# 467444_130_3_1-A.net
KiCad netlist of a schematic drawn in Altium Designer
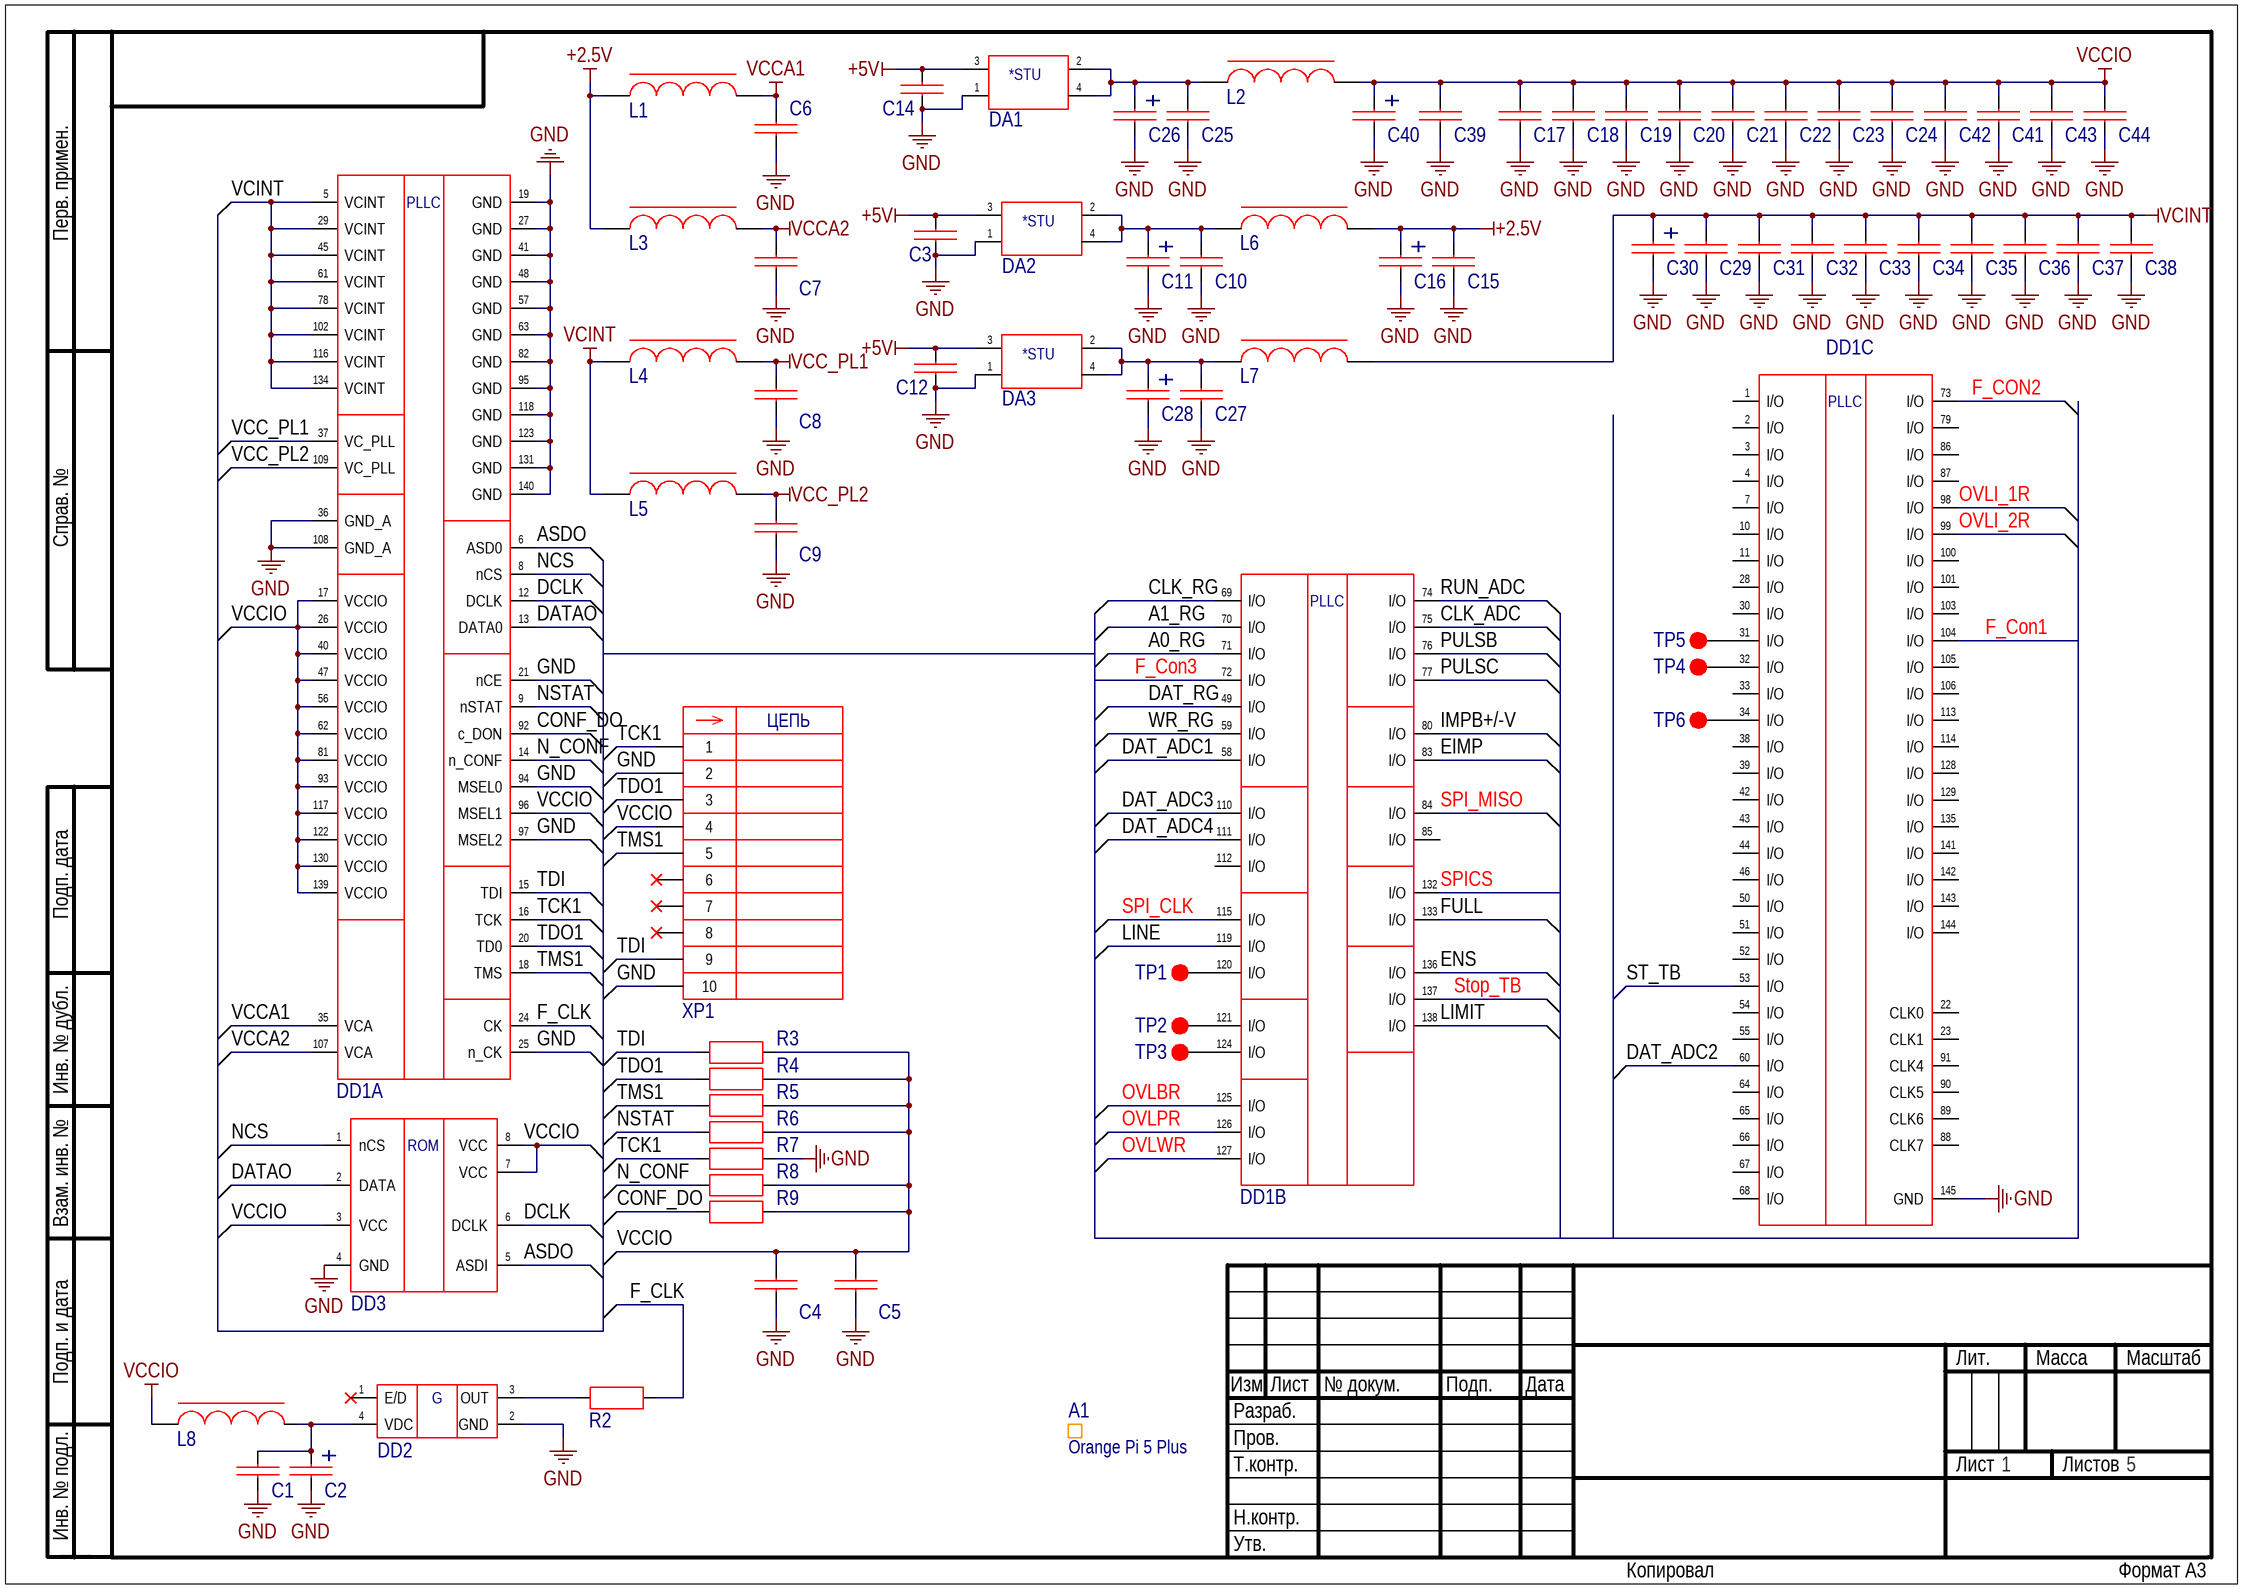
[diagram p0: УШЯИ.467444.130Э3_1-A.SchDoc]

(export (version "E")
  (design (tool "Eeschema 10.0.6"))
  (components
    (comp (ref "A1")
      (value "Orange Pi 5 Plus")
      (footprint "Orange_Pi_5_Plus")
      (description "8GB Rockchip RK3588, HDMI 2.1, Gigabit LAN port, USB2.0/3.0, microSD card slot, USB Type-C")
      (fields (field (name "MANUFACTURER") "Orange Pi"))
      (libsource (lib "lib") (part "0"))
    )
    (comp (ref "C1")
      (value "0,1 µF")
      (footprint "C_0805 [2012 Metric]")
      (description "Неполярный конденсатор")
      (fields (field (name "MANUFACTURER") "Murata") (field (name "VOLTAGE") "50V"))
      (libsource (lib "lib") (part "C_const"))
    )
    (comp (ref "C2")
      (value "4,7 µF")
      (footprint "C+_1210 [3528-21 Metric]")
      (description "Полярный конденсатор")
      (fields (field (name "MANUFACTURER") "KYOCERA AVX") (field (name "VOLTAGE") "20V\r\n10V"))
      (libsource (lib "lib") (part "C_electrolytic"))
    )
    (comp (ref "C3")
      (value "0,1 µF")
      (footprint "C_0805 [2012 Metric]")
      (description "Неполярный конденсатор")
      (fields (field (name "MANUFACTURER") "Murata") (field (name "VOLTAGE") "25V"))
      (libsource (lib "lib") (part "C_const"))
    )
    (comp (ref "C4")
      (value "1 µF")
      (footprint "C_0805 [2012 Metric]")
      (description "Неполярный конденсатор")
      (fields (field (name "MANUFACTURER") "Murata") (field (name "VOLTAGE") "16V"))
      (libsource (lib "lib") (part "C_const"))
    )
    (comp (ref "C5")
      (value "1 µF")
      (footprint "C_0805 [2012 Metric]")
      (description "Неполярный конденсатор")
      (fields (field (name "MANUFACTURER") "Murata") (field (name "VOLTAGE") "16V"))
      (libsource (lib "lib") (part "C_const"))
    )
    (comp (ref "C6")
      (value "0,1 µF")
      (footprint "C_0805 [2012 Metric]")
      (description "Неполярный конденсатор")
      (fields (field (name "MANUFACTURER") "Murata") (field (name "VOLTAGE") "25V"))
      (libsource (lib "lib") (part "C_const"))
    )
    (comp (ref "C7")
      (value "0,1 µF")
      (footprint "C_0805 [2012 Metric]")
      (description "Неполярный конденсатор")
      (fields (field (name "MANUFACTURER") "Murata") (field (name "VOLTAGE") "25V"))
      (libsource (lib "lib") (part "C_const"))
    )
    (comp (ref "C8")
      (value "0,1 µF")
      (footprint "C_0805 [2012 Metric]")
      (description "Неполярный конденсатор")
      (fields (field (name "MANUFACTURER") "Murata") (field (name "VOLTAGE") "25V"))
      (libsource (lib "lib") (part "C_const"))
    )
    (comp (ref "C9")
      (value "0,1 µF")
      (footprint "C_0805 [2012 Metric]")
      (description "Неполярный конденсатор")
      (fields (field (name "MANUFACTURER") "Murata") (field (name "VOLTAGE") "25V"))
      (libsource (lib "lib") (part "C_const"))
    )
    (comp (ref "C10")
      (value "0,1 µF")
      (footprint "C_0805 [2012 Metric]")
      (description "Неполярный конденсатор")
      (fields (field (name "MANUFACTURER") "Murata") (field (name "VOLTAGE") "25V"))
      (libsource (lib "lib") (part "C_const"))
    )
    (comp (ref "C11")
      (value "4,7 µF")
      (footprint "C+_1210 [3528-21 Metric]")
      (description "Полярный конденсатор")
      (fields (field (name "MANUFACTURER") "KYOCERA AVX") (field (name "VOLTAGE") "20V\r\n10V"))
      (libsource (lib "lib") (part "C_electrolytic"))
    )
    (comp (ref "C12")
      (value "0,1 µF")
      (footprint "C_0805 [2012 Metric]")
      (description "Неполярный конденсатор")
      (fields (field (name "MANUFACTURER") "Murata") (field (name "VOLTAGE") "25V"))
      (libsource (lib "lib") (part "C_const"))
    )
    (comp (ref "C14")
      (value "0,1 µF")
      (footprint "C_0805 [2012 Metric]")
      (description "Неполярный конденсатор")
      (fields (field (name "MANUFACTURER") "Murata") (field (name "VOLTAGE") "25V"))
      (libsource (lib "lib") (part "C_const"))
    )
    (comp (ref "C15")
      (value "0,1 µF")
      (footprint "C_0805 [2012 Metric]")
      (description "Неполярный конденсатор")
      (fields (field (name "MANUFACTURER") "Murata") (field (name "VOLTAGE") "25V"))
      (libsource (lib "lib") (part "C_const"))
    )
    (comp (ref "C16")
      (value "10 µF")
      (footprint "C+_1210 [3528-21 Metric]")
      (description "Полярный конденсатор")
      (fields (field (name "MANUFACTURER") "KYOCERA AVX") (field (name "VOLTAGE") "20V\r\n10V"))
      (libsource (lib "lib") (part "C_electrolytic"))
    )
    (comp (ref "C17")
      (value "0,1 µF")
      (footprint "C_0805 [2012 Metric]")
      (description "Неполярный конденсатор")
      (fields (field (name "MANUFACTURER") "Murata") (field (name "VOLTAGE") "25V"))
      (libsource (lib "lib") (part "C_const"))
    )
    (comp (ref "C18")
      (value "0,1 µF")
      (footprint "C_0805 [2012 Metric]")
      (description "Неполярный конденсатор")
      (fields (field (name "MANUFACTURER") "Murata") (field (name "VOLTAGE") "25V"))
      (libsource (lib "lib") (part "C_const"))
    )
    (comp (ref "C19")
      (value "0,1 µF")
      (footprint "C_0805 [2012 Metric]")
      (description "Неполярный конденсатор")
      (fields (field (name "MANUFACTURER") "Murata") (field (name "VOLTAGE") "25V"))
      (libsource (lib "lib") (part "C_const"))
    )
    (comp (ref "C20")
      (value "0,1 µF")
      (footprint "C_0805 [2012 Metric]")
      (description "Неполярный конденсатор")
      (fields (field (name "MANUFACTURER") "Murata") (field (name "VOLTAGE") "25V"))
      (libsource (lib "lib") (part "C_const"))
    )
    (comp (ref "C21")
      (value "0,1 µF")
      (footprint "C_0805 [2012 Metric]")
      (description "Неполярный конденсатор")
      (fields (field (name "MANUFACTURER") "Murata") (field (name "VOLTAGE") "25V"))
      (libsource (lib "lib") (part "C_const"))
    )
    (comp (ref "C22")
      (value "0,1 µF")
      (footprint "C_0805 [2012 Metric]")
      (description "Неполярный конденсатор")
      (fields (field (name "MANUFACTURER") "Murata") (field (name "VOLTAGE") "25V"))
      (libsource (lib "lib") (part "C_const"))
    )
    (comp (ref "C23")
      (value "0,1 µF")
      (footprint "C_0805 [2012 Metric]")
      (description "Неполярный конденсатор")
      (fields (field (name "MANUFACTURER") "Murata") (field (name "VOLTAGE") "25V"))
      (libsource (lib "lib") (part "C_const"))
    )
    (comp (ref "C24")
      (value "0,1 µF")
      (footprint "C_0805 [2012 Metric]")
      (description "Неполярный конденсатор")
      (fields (field (name "MANUFACTURER") "Murata") (field (name "VOLTAGE") "25V"))
      (libsource (lib "lib") (part "C_const"))
    )
    (comp (ref "C25")
      (value "0,1 µF")
      (footprint "C_0805 [2012 Metric]")
      (description "Неполярный конденсатор")
      (fields (field (name "MANUFACTURER") "Murata") (field (name "VOLTAGE") "25V"))
      (libsource (lib "lib") (part "C_const"))
    )
    (comp (ref "C26")
      (value "4,7 µF")
      (footprint "C+_1210 [3528-21 Metric]")
      (description "Полярный конденсатор")
      (fields (field (name "MANUFACTURER") "KYOCERA AVX") (field (name "VOLTAGE") "20V\r\n10V"))
      (libsource (lib "lib") (part "C_electrolytic"))
    )
    (comp (ref "C27")
      (value "0,1 µF")
      (footprint "C_0805 [2012 Metric]")
      (description "Неполярный конденсатор")
      (fields (field (name "MANUFACTURER") "Murata") (field (name "VOLTAGE") "50V"))
      (libsource (lib "lib") (part "C_const"))
    )
    (comp (ref "C28")
      (value "4,7 µF")
      (footprint "C+_1210 [3528-21 Metric]")
      (description "Полярный конденсатор")
      (fields (field (name "MANUFACTURER") "KYOCERA AVX") (field (name "VOLTAGE") "20V\r\n10V"))
      (libsource (lib "lib") (part "C_electrolytic"))
    )
    (comp (ref "C29")
      (value "0,1 µF")
      (footprint "C_0805 [2012 Metric]")
      (description "Неполярный конденсатор")
      (fields (field (name "MANUFACTURER") "Murata") (field (name "VOLTAGE") "50V"))
      (libsource (lib "lib") (part "C_const"))
    )
    (comp (ref "C30")
      (value "4,7 µF")
      (footprint "C+_1210 [3528-21 Metric]")
      (description "Полярный конденсатор")
      (fields (field (name "MANUFACTURER") "KYOCERA AVX") (field (name "VOLTAGE") "20V\r\n10V"))
      (libsource (lib "lib") (part "C_electrolytic"))
    )
    (comp (ref "C31")
      (value "0,1 µF")
      (footprint "C_0805 [2012 Metric]")
      (description "Неполярный конденсатор")
      (fields (field (name "MANUFACTURER") "Murata") (field (name "VOLTAGE") "50V"))
      (libsource (lib "lib") (part "C_const"))
    )
    (comp (ref "C32")
      (value "0,1 µF")
      (footprint "C_0805 [2012 Metric]")
      (description "Неполярный конденсатор")
      (fields (field (name "MANUFACTURER") "Murata") (field (name "VOLTAGE") "50V"))
      (libsource (lib "lib") (part "C_const"))
    )
    (comp (ref "C33")
      (value "0,1 µF")
      (footprint "C_0805 [2012 Metric]")
      (description "Неполярный конденсатор")
      (fields (field (name "MANUFACTURER") "Murata") (field (name "VOLTAGE") "50V"))
      (libsource (lib "lib") (part "C_const"))
    )
    (comp (ref "C34")
      (value "0,1 µF")
      (footprint "C_0805 [2012 Metric]")
      (description "Неполярный конденсатор")
      (fields (field (name "MANUFACTURER") "Murata") (field (name "VOLTAGE") "50V"))
      (libsource (lib "lib") (part "C_const"))
    )
    (comp (ref "C35")
      (value "0,1 µF")
      (footprint "C_0805 [2012 Metric]")
      (description "Неполярный конденсатор")
      (fields (field (name "MANUFACTURER") "Murata") (field (name "VOLTAGE") "50V"))
      (libsource (lib "lib") (part "C_const"))
    )
    (comp (ref "C36")
      (value "0,1 µF")
      (footprint "C_0805 [2012 Metric]")
      (description "Неполярный конденсатор")
      (fields (field (name "MANUFACTURER") "Murata") (field (name "VOLTAGE") "50V"))
      (libsource (lib "lib") (part "C_const"))
    )
    (comp (ref "C37")
      (value "0,1 µF")
      (footprint "C_0805 [2012 Metric]")
      (description "Неполярный конденсатор")
      (fields (field (name "MANUFACTURER") "Murata") (field (name "VOLTAGE") "50V"))
      (libsource (lib "lib") (part "C_const"))
    )
    (comp (ref "C38")
      (value "0,1 µF")
      (footprint "C_0805 [2012 Metric]")
      (description "Неполярный конденсатор")
      (fields (field (name "MANUFACTURER") "Murata") (field (name "VOLTAGE") "50V"))
      (libsource (lib "lib") (part "C_const"))
    )
    (comp (ref "C39")
      (value "0,1 µF")
      (footprint "C_0805 [2012 Metric]")
      (description "Неполярный конденсатор")
      (fields (field (name "MANUFACTURER") "Murata") (field (name "VOLTAGE") "50V"))
      (libsource (lib "lib") (part "C_const"))
    )
    (comp (ref "C40")
      (value "10 µF")
      (footprint "C+_1210 [3528-21 Metric]")
      (description "Полярный конденсатор")
      (fields (field (name "MANUFACTURER") "KYOCERA AVX") (field (name "VOLTAGE") "20V\r\n10V"))
      (libsource (lib "lib") (part "C_electrolytic"))
    )
    (comp (ref "C41")
      (value "0,1 µF")
      (footprint "C_0805 [2012 Metric]")
      (description "Неполярный конденсатор")
      (fields (field (name "MANUFACTURER") "Murata") (field (name "VOLTAGE") "50V"))
      (libsource (lib "lib") (part "C_const"))
    )
    (comp (ref "C42")
      (value "0,1 µF")
      (footprint "C_0805 [2012 Metric]")
      (description "Неполярный конденсатор")
      (fields (field (name "MANUFACTURER") "Murata") (field (name "VOLTAGE") "50V"))
      (libsource (lib "lib") (part "C_const"))
    )
    (comp (ref "C43")
      (value "0,1 µF")
      (footprint "C_0805 [2012 Metric]")
      (description "Неполярный конденсатор")
      (fields (field (name "MANUFACTURER") "Murata") (field (name "VOLTAGE") "50V"))
      (libsource (lib "lib") (part "C_const"))
    )
    (comp (ref "C44")
      (value "0,1 µF")
      (footprint "C_0805 [2012 Metric]")
      (description "Неполярный конденсатор")
      (fields (field (name "MANUFACTURER") "Murata") (field (name "VOLTAGE") "50V"))
      (libsource (lib "lib") (part "C_const"))
    )
    (comp (ref "DA1")
      (value "LD1117AS33TR")
      (footprint "SOT-223")
      (description "IC, Fixed LDO Voltage Regulator, 5.3V to 10V, 1.15V Dropout, 3.3Vout, 1Aout")
      (fields (field (name "MANUFACTURER") "STMicroelectronics"))
      (libsource (lib "lib") (part "VolReg_LD1117AS33TR"))
    )
    (comp (ref "DA2")
      (value "LD1117AS25TR")
      (footprint "SOT-223")
      (description "IC, Linear Voltage Regulator, 1 Output, 1V Dropout, 2.5Vout, 1Aout")
      (fields (field (name "MANUFACTURER") "STMicroelectronics"))
      (libsource (lib "lib") (part "VolReg_LD1117AS33TR"))
    )
    (comp (ref "DA3")
      (value "LD1117AS12TR")
      (footprint "SOT-223")
      (description "IC, Fixed LDO Voltage Regulator, 1 Output, 1V Dropout, 1.2Vout, 1Aout")
      (fields (field (name "MANUFACTURER") "STMicroelectronics"))
      (libsource (lib "lib") (part "VolReg_LD1117AS33TR"))
    )
    (comp (ref "DD1")
      (value "EP3C5E144I7")
      (footprint "EQFP-144[20x20]_0.5_22x22x1.6")
      (description "IC, Cyclone III, Field Programmable Gate Array (FPGA), 	1.15V to 1.25V, 315 MHz, 94 I/O")
      (fields (field (name "MANUFACTURER") "Intel"))
      (libsource (lib "lib") (part "EP3C5E144I7"))
    )
    (comp (ref "DD2")
      (value "O 20,0-JO32-B-3.3-1-T1-LF")
      (footprint "JO32")
      (description "Crystals, Oscillators, 20 MHz")
      (fields (field (name "MANUFACTURER") "Jauch Quartz GmbH"))
      (libsource (lib "lib") (part "JO32"))
    )
    (comp (ref "DD3")
      (value "EPCS4SI8N")
      (footprint "SOIC-8_1.27_5x4x1.75")
      (description "IC, FPGA Configuration Memory, Flash, 4 Mbit, 40 MHz, JTAG, Serial")
      (fields (field (name "MANUFACTURER") "Intel"))
      (libsource (lib "lib") (part "EPCS4"))
    )
    (comp (ref "L1")
      (value "0,22 μH")
      (footprint "IND_LQH31CN")
      (fields (field (name "MANUFACTURER") "Murata") (field (name "TOLERANCE") "±20%"))
      (libsource (lib "lib") (part "IND_ferromagnetic/ferrite_core"))
    )
    (comp (ref "L2")
      (value "~")
      (footprint "IND_0805 [2012 Metric]")
      (fields (field (name "MANUFACTURER") "Vishay") (field (name "TOLERANCE") "±25%"))
      (libsource (lib "lib") (part "IND_ferromagnetic/ferrite_core"))
    )
    (comp (ref "L3")
      (value "0,22 μH")
      (footprint "IND_LQH31CN")
      (fields (field (name "MANUFACTURER") "Murata") (field (name "TOLERANCE") "±20%"))
      (libsource (lib "lib") (part "IND_ferromagnetic/ferrite_core"))
    )
    (comp (ref "L4")
      (value "0,22 μH")
      (footprint "IND_LQH31CN")
      (fields (field (name "MANUFACTURER") "Murata") (field (name "TOLERANCE") "±20%"))
      (libsource (lib "lib") (part "IND_ferromagnetic/ferrite_core"))
    )
    (comp (ref "L5")
      (value "0,22 μH")
      (footprint "IND_LQH31CN")
      (fields (field (name "MANUFACTURER") "Murata") (field (name "TOLERANCE") "±20%"))
      (libsource (lib "lib") (part "IND_ferromagnetic/ferrite_core"))
    )
    (comp (ref "L6")
      (value "~")
      (footprint "IND_0805 [2012 Metric]")
      (fields (field (name "MANUFACTURER") "Vishay") (field (name "TOLERANCE") "±25%"))
      (libsource (lib "lib") (part "IND_ferromagnetic/ferrite_core"))
    )
    (comp (ref "L7")
      (value "~")
      (footprint "IND_0805 [2012 Metric]")
      (fields (field (name "MANUFACTURER") "Vishay") (field (name "TOLERANCE") "±25%"))
      (libsource (lib "lib") (part "IND_ferromagnetic/ferrite_core"))
    )
    (comp (ref "L8")
      (value "~")
      (footprint "IND_0805 [2012 Metric]")
      (fields (field (name "MANUFACTURER") "Vishay") (field (name "TOLERANCE") "±25%"))
      (libsource (lib "lib") (part "IND_ferromagnetic/ferrite_core"))
    )
    (comp (ref "R2")
      (value "51R")
      (footprint "R_0805 [2012 Metric]")
      (fields (field (name "TOLERANCE") "±5%"))
      (libsource (lib "lib") (part "R_Const"))
    )
    (comp (ref "R3")
      (value "1k")
      (footprint "R_0805 [2012 Metric]")
      (fields (field (name "TOLERANCE") "±5%"))
      (libsource (lib "lib") (part "R_Const"))
    )
    (comp (ref "R4")
      (value "10k")
      (footprint "R_0805 [2012 Metric]")
      (fields (field (name "TOLERANCE") "±5%"))
      (libsource (lib "lib") (part "R_Const"))
    )
    (comp (ref "R5")
      (value "1k")
      (footprint "R_0805 [2012 Metric]")
      (fields (field (name "TOLERANCE") "±5%"))
      (libsource (lib "lib") (part "R_Const"))
    )
    (comp (ref "R6")
      (value "10k")
      (footprint "R_0805 [2012 Metric]")
      (fields (field (name "TOLERANCE") "±5%"))
      (libsource (lib "lib") (part "R_Const"))
    )
    (comp (ref "R7")
      (value "1k")
      (footprint "R_0805 [2012 Metric]")
      (fields (field (name "TOLERANCE") "±5%"))
      (libsource (lib "lib") (part "R_Const"))
    )
    (comp (ref "R8")
      (value "10k")
      (footprint "R_0805 [2012 Metric]")
      (fields (field (name "TOLERANCE") "±5%"))
      (libsource (lib "lib") (part "R_Const"))
    )
    (comp (ref "R9")
      (value "10k")
      (footprint "R_0805 [2012 Metric]")
      (fields (field (name "TOLERANCE") "±5%"))
      (libsource (lib "lib") (part "R_Const"))
    )
    (comp (ref "TP1") (value "~") (footprint "DSP_1.3") (libsource (lib "lib") (part "TP")))
    (comp (ref "TP2") (value "~") (footprint "DSP_1.3") (libsource (lib "lib") (part "TP")))
    (comp (ref "TP3") (value "~") (footprint "DSP_1.3") (libsource (lib "lib") (part "TP")))
    (comp (ref "TP4") (value "~") (footprint "DSP_1.3") (libsource (lib "lib") (part "TP")))
    (comp (ref "TP5") (value "~") (footprint "DSP_1.3") (libsource (lib "lib") (part "TP")))
    (comp (ref "TP6") (value "~") (footprint "DSP_1.3") (libsource (lib "lib") (part "TP")))
    (comp (ref "XP1")
      (value "PLD-10")
      (footprint "PLD-10")
      (description "Male, 10 pins, 2 rows, Vertical")
      (fields (field (name "MANUFACTURER") "Connfly electronic"))
      (libsource (lib "lib") (part "M_10"))
    )
  )
  (nets
    (net (code "1") (name "+2.5V") (class "Default")
      (node (ref "C15") (pin "2") (pinfunction "2_2") (pintype "passive"))
      (node (ref "C16") (pin "+") (pinfunction "+_+") (pintype "passive"))
      (node (ref "L1") (pin "1") (pinfunction "1_1") (pintype "passive"))
      (node (ref "L3") (pin "1") (pinfunction "1_1") (pintype "passive"))
      (node (ref "L6") (pin "2") (pinfunction "2_2") (pintype "passive"))
    )
    (net (code "2") (name "+5V") (class "Default")
      (node (ref "C12") (pin "2") (pinfunction "2_2") (pintype "passive"))
      (node (ref "C14") (pin "2") (pinfunction "2_2") (pintype "passive"))
      (node (ref "C3") (pin "2") (pinfunction "2_2") (pintype "passive"))
      (node (ref "DA1") (pin "3") (pinfunction "VIN_3") (pintype "passive"))
      (node (ref "DA2") (pin "3") (pinfunction "VIN_3") (pintype "passive"))
      (node (ref "DA3") (pin "3") (pinfunction "VIN_3") (pintype "passive"))
    )
    (net (code "3") (name "/A0_RG") (class "Default")
      (node (ref "DD1") (pin "71") (pinfunction "I/O_71") (pintype "passive"))
    )
    (net (code "4") (name "/A1_RG") (class "Default")
      (node (ref "DD1") (pin "70") (pinfunction "I/O_70") (pintype "passive"))
    )
    (net (code "5") (name "/ASDO") (class "Default")
      (node (ref "DD1") (pin "6") (pinfunction "ASD0_6") (pintype "passive"))
      (node (ref "DD3") (pin "5") (pinfunction "ASDI_5") (pintype "passive"))
    )
    (net (code "6") (name "/CLK_ADC") (class "Default")
      (node (ref "DD1") (pin "75") (pinfunction "I/O_75") (pintype "passive"))
    )
    (net (code "7") (name "/CLK_RG") (class "Default")
      (node (ref "DD1") (pin "69") (pinfunction "I/O_69") (pintype "passive"))
    )
    (net (code "8") (name "/CONF_DO") (class "Default")
      (node (ref "DD1") (pin "92") (pinfunction "c_DON_92") (pintype "passive"))
      (node (ref "R9") (pin "1") (pinfunction "1_1") (pintype "passive"))
    )
    (net (code "9") (name "/DATAO") (class "Default")
      (node (ref "DD1") (pin "13") (pinfunction "DATA0_13") (pintype "passive"))
      (node (ref "DD3") (pin "2") (pinfunction "DATA_2") (pintype "passive"))
    )
    (net (code "10") (name "/DAT_ADC1") (class "Default")
      (node (ref "DD1") (pin "58") (pinfunction "I/O_58") (pintype "passive"))
    )
    (net (code "11") (name "/DAT_ADC2") (class "Default")
      (node (ref "DD1") (pin "60") (pinfunction "I/O_60") (pintype "passive"))
    )
    (net (code "12") (name "/DAT_ADC3") (class "Default")
      (node (ref "DD1") (pin "110") (pinfunction "I/O_110") (pintype "passive"))
    )
    (net (code "13") (name "/DAT_ADC4") (class "Default")
      (node (ref "DD1") (pin "111") (pinfunction "I/O_111") (pintype "passive"))
    )
    (net (code "14") (name "/DAT_RG") (class "Default")
      (node (ref "DD1") (pin "49") (pinfunction "I/O_49") (pintype "passive"))
    )
    (net (code "15") (name "/DCLK") (class "Default")
      (node (ref "DD1") (pin "12") (pinfunction "DCLK_12") (pintype "passive"))
      (node (ref "DD3") (pin "6") (pinfunction "DCLK_6") (pintype "passive"))
    )
    (net (code "16") (name "/EIMP") (class "Default")
      (node (ref "DD1") (pin "83") (pinfunction "I/O_83") (pintype "passive"))
    )
    (net (code "17") (name "/ENS") (class "Default")
      (node (ref "DD1") (pin "136") (pinfunction "I/O_136") (pintype "passive"))
    )
    (net (code "18") (name "/FULL") (class "Default")
      (node (ref "DD1") (pin "133") (pinfunction "I/O_133") (pintype "passive"))
    )
    (net (code "19") (name "/F_CLK") (class "Default")
      (node (ref "DD1") (pin "24") (pinfunction "CK_24") (pintype "passive"))
      (node (ref "R2") (pin "2") (pinfunction "2_2") (pintype "passive"))
    )
    (net (code "20") (name "/F_CON2") (class "Default")
      (node (ref "DD1") (pin "73") (pinfunction "I/O_73") (pintype "passive"))
    )
    (net (code "21") (name "/F_Con1") (class "Default")
      (node (ref "DD1") (pin "104") (pinfunction "I/O_104") (pintype "passive"))
    )
    (net (code "22") (name "/F_Con3") (class "Default")
      (node (ref "DD1") (pin "72") (pinfunction "I/O_72") (pintype "passive"))
    )
    (net (code "23") (name "/IMPB+{slash}-V") (class "Default")
      (node (ref "DD1") (pin "80") (pinfunction "I/O_80") (pintype "passive"))
    )
    (net (code "24") (name "/LIMIT") (class "Default")
      (node (ref "DD1") (pin "138") (pinfunction "I/O_138") (pintype "passive"))
    )
    (net (code "25") (name "/LINE") (class "Default")
      (node (ref "DD1") (pin "119") (pinfunction "I/O_119") (pintype "passive"))
    )
    (net (code "26") (name "/NCS") (class "Default")
      (node (ref "DD1") (pin "8") (pinfunction "nCS_8") (pintype "passive"))
      (node (ref "DD3") (pin "1") (pinfunction "nCS_1") (pintype "passive"))
    )
    (net (code "27") (name "/NSTAT") (class "Default")
      (node (ref "DD1") (pin "9") (pinfunction "nSTAT_9") (pintype "passive"))
      (node (ref "R6") (pin "1") (pinfunction "1_1") (pintype "passive"))
    )
    (net (code "28") (name "/N_CONF") (class "Default")
      (node (ref "DD1") (pin "14") (pinfunction "n_CONF_14") (pintype "passive"))
      (node (ref "R8") (pin "1") (pinfunction "1_1") (pintype "passive"))
    )
    (net (code "29") (name "/OVLBR") (class "Default")
      (node (ref "DD1") (pin "125") (pinfunction "I/O_125") (pintype "passive"))
    )
    (net (code "30") (name "/OVLI_1R") (class "Default")
      (node (ref "DD1") (pin "98") (pinfunction "I/O_98") (pintype "passive"))
    )
    (net (code "31") (name "/OVLI_2R") (class "Default")
      (node (ref "DD1") (pin "99") (pinfunction "I/O_99") (pintype "passive"))
    )
    (net (code "32") (name "/OVLPR") (class "Default")
      (node (ref "DD1") (pin "126") (pinfunction "I/O_126") (pintype "passive"))
    )
    (net (code "33") (name "/OVLWR") (class "Default")
      (node (ref "DD1") (pin "127") (pinfunction "I/O_127") (pintype "passive"))
    )
    (net (code "34") (name "/PULSB") (class "Default")
      (node (ref "DD1") (pin "76") (pinfunction "I/O_76") (pintype "passive"))
    )
    (net (code "35") (name "/PULSC") (class "Default")
      (node (ref "DD1") (pin "77") (pinfunction "I/O_77") (pintype "passive"))
    )
    (net (code "36") (name "/RUN_ADC") (class "Default")
      (node (ref "DD1") (pin "74") (pinfunction "I/O_74") (pintype "passive"))
    )
    (net (code "37") (name "/SPICS") (class "Default")
      (node (ref "DD1") (pin "132") (pinfunction "I/O_132") (pintype "passive"))
    )
    (net (code "38") (name "/SPI_CLK") (class "Default")
      (node (ref "DD1") (pin "115") (pinfunction "I/O_115") (pintype "passive"))
    )
    (net (code "39") (name "/SPI_MISO") (class "Default")
      (node (ref "DD1") (pin "84") (pinfunction "I/O_84") (pintype "passive"))
    )
    (net (code "40") (name "/ST_TB") (class "Default")
      (node (ref "DD1") (pin "53") (pinfunction "I/O_53") (pintype "passive"))
    )
    (net (code "41") (name "/Stop_TB") (class "Default")
      (node (ref "DD1") (pin "137") (pinfunction "I/O_137") (pintype "passive"))
    )
    (net (code "42") (name "/TCK1") (class "Default")
      (node (ref "DD1") (pin "16") (pinfunction "TCK_16") (pintype "passive"))
      (node (ref "R7") (pin "1") (pinfunction "1_1") (pintype "passive"))
      (node (ref "XP1") (pin "1") (pinfunction "1_1") (pintype "passive"))
    )
    (net (code "43") (name "/TDI") (class "Default")
      (node (ref "DD1") (pin "15") (pinfunction "TDI_15") (pintype "passive"))
      (node (ref "R3") (pin "1") (pinfunction "1_1") (pintype "passive"))
      (node (ref "XP1") (pin "9") (pinfunction "9_9") (pintype "passive"))
    )
    (net (code "44") (name "/TDO1") (class "Default")
      (node (ref "DD1") (pin "20") (pinfunction "TD0_20") (pintype "passive"))
      (node (ref "R4") (pin "1") (pinfunction "1_1") (pintype "passive"))
      (node (ref "XP1") (pin "3") (pinfunction "3_3") (pintype "passive"))
    )
    (net (code "45") (name "/TMS1") (class "Default")
      (node (ref "DD1") (pin "18") (pinfunction "TMS_18") (pintype "passive"))
      (node (ref "R5") (pin "1") (pinfunction "1_1") (pintype "passive"))
      (node (ref "XP1") (pin "5") (pinfunction "5_5") (pintype "passive"))
    )
    (net (code "46") (name "/WR_RG") (class "Default")
      (node (ref "DD1") (pin "59") (pinfunction "I/O_59") (pintype "passive"))
    )
    (net (code "47") (name "GND") (class "Default")
      (node (ref "C1") (pin "1") (pinfunction "1_1") (pintype "passive"))
      (node (ref "C10") (pin "1") (pinfunction "1_1") (pintype "passive"))
      (node (ref "C11") (pin "-") (pinfunction "-_-") (pintype "passive"))
      (node (ref "C12") (pin "1") (pinfunction "1_1") (pintype "passive"))
      (node (ref "C14") (pin "1") (pinfunction "1_1") (pintype "passive"))
      (node (ref "C15") (pin "1") (pinfunction "1_1") (pintype "passive"))
      (node (ref "C16") (pin "-") (pinfunction "-_-") (pintype "passive"))
      (node (ref "C17") (pin "1") (pinfunction "1_1") (pintype "passive"))
      (node (ref "C18") (pin "1") (pinfunction "1_1") (pintype "passive"))
      (node (ref "C19") (pin "1") (pinfunction "1_1") (pintype "passive"))
      (node (ref "C2") (pin "-") (pinfunction "-_-") (pintype "passive"))
      (node (ref "C20") (pin "1") (pinfunction "1_1") (pintype "passive"))
      (node (ref "C21") (pin "1") (pinfunction "1_1") (pintype "passive"))
      (node (ref "C22") (pin "1") (pinfunction "1_1") (pintype "passive"))
      (node (ref "C23") (pin "1") (pinfunction "1_1") (pintype "passive"))
      (node (ref "C24") (pin "1") (pinfunction "1_1") (pintype "passive"))
      (node (ref "C25") (pin "1") (pinfunction "1_1") (pintype "passive"))
      (node (ref "C26") (pin "-") (pinfunction "-_-") (pintype "passive"))
      (node (ref "C27") (pin "1") (pinfunction "1_1") (pintype "passive"))
      (node (ref "C28") (pin "-") (pinfunction "-_-") (pintype "passive"))
      (node (ref "C29") (pin "1") (pinfunction "1_1") (pintype "passive"))
      (node (ref "C3") (pin "1") (pinfunction "1_1") (pintype "passive"))
      (node (ref "C30") (pin "-") (pinfunction "-_-") (pintype "passive"))
      (node (ref "C31") (pin "1") (pinfunction "1_1") (pintype "passive"))
      (node (ref "C32") (pin "1") (pinfunction "1_1") (pintype "passive"))
      (node (ref "C33") (pin "1") (pinfunction "1_1") (pintype "passive"))
      (node (ref "C34") (pin "1") (pinfunction "1_1") (pintype "passive"))
      (node (ref "C35") (pin "1") (pinfunction "1_1") (pintype "passive"))
      (node (ref "C36") (pin "1") (pinfunction "1_1") (pintype "passive"))
      (node (ref "C37") (pin "1") (pinfunction "1_1") (pintype "passive"))
      (node (ref "C38") (pin "1") (pinfunction "1_1") (pintype "passive"))
      (node (ref "C39") (pin "1") (pinfunction "1_1") (pintype "passive"))
      (node (ref "C4") (pin "1") (pinfunction "1_1") (pintype "passive"))
      (node (ref "C40") (pin "-") (pinfunction "-_-") (pintype "passive"))
      (node (ref "C41") (pin "1") (pinfunction "1_1") (pintype "passive"))
      (node (ref "C42") (pin "1") (pinfunction "1_1") (pintype "passive"))
      (node (ref "C43") (pin "1") (pinfunction "1_1") (pintype "passive"))
      (node (ref "C44") (pin "1") (pinfunction "1_1") (pintype "passive"))
      (node (ref "C5") (pin "1") (pinfunction "1_1") (pintype "passive"))
      (node (ref "C6") (pin "1") (pinfunction "1_1") (pintype "passive"))
      (node (ref "C7") (pin "1") (pinfunction "1_1") (pintype "passive"))
      (node (ref "C8") (pin "1") (pinfunction "1_1") (pintype "passive"))
      (node (ref "C9") (pin "1") (pinfunction "1_1") (pintype "passive"))
      (node (ref "DA1") (pin "1") (pinfunction "ADJ/GND_1") (pintype "passive"))
      (node (ref "DA2") (pin "1") (pinfunction "ADJ/GND_1") (pintype "passive"))
      (node (ref "DA3") (pin "1") (pinfunction "ADJ/GND_1") (pintype "passive"))
      (node (ref "DD1") (pin "108") (pinfunction "GND_A_108") (pintype "passive"))
      (node (ref "DD1") (pin "118") (pinfunction "GND_118") (pintype "passive"))
      (node (ref "DD1") (pin "123") (pinfunction "GND_123") (pintype "passive"))
      (node (ref "DD1") (pin "131") (pinfunction "GND_131") (pintype "passive"))
      (node (ref "DD1") (pin "140") (pinfunction "GND_140") (pintype "passive"))
      (node (ref "DD1") (pin "145") (pinfunction "GND_145") (pintype "passive"))
      (node (ref "DD1") (pin "19") (pinfunction "GND_19") (pintype "passive"))
      (node (ref "DD1") (pin "21") (pinfunction "nCE_21") (pintype "passive"))
      (node (ref "DD1") (pin "25") (pinfunction "n_CK_25") (pintype "passive"))
      (node (ref "DD1") (pin "27") (pinfunction "GND_27") (pintype "passive"))
      (node (ref "DD1") (pin "36") (pinfunction "GND_A_36") (pintype "passive"))
      (node (ref "DD1") (pin "41") (pinfunction "GND_41") (pintype "passive"))
      (node (ref "DD1") (pin "48") (pinfunction "GND_48") (pintype "passive"))
      (node (ref "DD1") (pin "57") (pinfunction "GND_57") (pintype "passive"))
      (node (ref "DD1") (pin "63") (pinfunction "GND_63") (pintype "passive"))
      (node (ref "DD1") (pin "82") (pinfunction "GND_82") (pintype "passive"))
      (node (ref "DD1") (pin "94") (pinfunction "MSEL0_94") (pintype "passive"))
      (node (ref "DD1") (pin "95") (pinfunction "GND_95") (pintype "passive"))
      (node (ref "DD1") (pin "97") (pinfunction "MSEL2_97") (pintype "passive"))
      (node (ref "DD2") (pin "2") (pinfunction "GND_2") (pintype "passive"))
      (node (ref "DD3") (pin "4") (pinfunction "GND_4") (pintype "passive"))
      (node (ref "R7") (pin "2") (pinfunction "2_2") (pintype "passive"))
      (node (ref "XP1") (pin "10") (pinfunction "10_10") (pintype "passive"))
      (node (ref "XP1") (pin "2") (pinfunction "2_2") (pintype "passive"))
    )
    (net (code "48") (name "Net-(C10-Pad2)") (class "Default")
      (node (ref "C10") (pin "2") (pinfunction "2_2") (pintype "passive"))
      (node (ref "C11") (pin "+") (pinfunction "+_+") (pintype "passive"))
      (node (ref "DA2") (pin "2") (pinfunction "VOUT_2") (pintype "passive"))
      (node (ref "DA2") (pin "4") (pinfunction "VOUT_4") (pintype "passive"))
      (node (ref "L6") (pin "1") (pinfunction "1_1") (pintype "passive"))
    )
    (net (code "49") (name "Net-(C25-Pad2)") (class "Default")
      (node (ref "C25") (pin "2") (pinfunction "2_2") (pintype "passive"))
      (node (ref "C26") (pin "+") (pinfunction "+_+") (pintype "passive"))
      (node (ref "DA1") (pin "2") (pinfunction "VOUT_2") (pintype "passive"))
      (node (ref "DA1") (pin "4") (pinfunction "VOUT_4") (pintype "passive"))
      (node (ref "L2") (pin "1") (pinfunction "1_1") (pintype "passive"))
    )
    (net (code "50") (name "Net-(C27-Pad2)") (class "Default")
      (node (ref "C27") (pin "2") (pinfunction "2_2") (pintype "passive"))
      (node (ref "C28") (pin "+") (pinfunction "+_+") (pintype "passive"))
      (node (ref "DA3") (pin "2") (pinfunction "VOUT_2") (pintype "passive"))
      (node (ref "DA3") (pin "4") (pinfunction "VOUT_4") (pintype "passive"))
      (node (ref "L7") (pin "1") (pinfunction "1_1") (pintype "passive"))
    )
    (net (code "51") (name "Net-(DD1B-I{slash}O-Pad120)") (class "Default")
      (node (ref "DD1") (pin "120") (pinfunction "I/O_120") (pintype "passive"))
      (node (ref "TP1") (pin "1") (pinfunction "1_1") (pintype "passive"))
    )
    (net (code "52") (name "Net-(DD1B-I{slash}O-Pad121)") (class "Default")
      (node (ref "DD1") (pin "121") (pinfunction "I/O_121") (pintype "passive"))
      (node (ref "TP2") (pin "1") (pinfunction "1_1") (pintype "passive"))
    )
    (net (code "53") (name "Net-(DD1B-I{slash}O-Pad124)") (class "Default")
      (node (ref "DD1") (pin "124") (pinfunction "I/O_124") (pintype "passive"))
      (node (ref "TP3") (pin "1") (pinfunction "1_1") (pintype "passive"))
    )
    (net (code "54") (name "Net-(DD1C-I{slash}O-Pad31)") (class "Default")
      (node (ref "DD1") (pin "31") (pinfunction "I/O_31") (pintype "passive"))
      (node (ref "TP5") (pin "1") (pinfunction "1_1") (pintype "passive"))
    )
    (net (code "55") (name "Net-(DD1C-I{slash}O-Pad32)") (class "Default")
      (node (ref "DD1") (pin "32") (pinfunction "I/O_32") (pintype "passive"))
      (node (ref "TP4") (pin "1") (pinfunction "1_1") (pintype "passive"))
    )
    (net (code "56") (name "Net-(DD1C-I{slash}O-Pad34)") (class "Default")
      (node (ref "DD1") (pin "34") (pinfunction "I/O_34") (pintype "passive"))
      (node (ref "TP6") (pin "1") (pinfunction "1_1") (pintype "passive"))
    )
    (net (code "57") (name "Net-(DD2-OUT)") (class "Default")
      (node (ref "DD2") (pin "3") (pinfunction "OUT_3") (pintype "passive"))
      (node (ref "R2") (pin "1") (pinfunction "1_1") (pintype "passive"))
    )
    (net (code "58") (name "Net-(DD2-VDC)") (class "Default")
      (node (ref "C1") (pin "2") (pinfunction "2_2") (pintype "passive"))
      (node (ref "C2") (pin "+") (pinfunction "+_+") (pintype "passive"))
      (node (ref "DD2") (pin "4") (pinfunction "VDC_4") (pintype "passive"))
      (node (ref "L8") (pin "2") (pinfunction "2_2") (pintype "passive"))
    )
    (net (code "59") (name "VCCA1") (class "Default")
      (node (ref "C6") (pin "2") (pinfunction "2_2") (pintype "passive"))
      (node (ref "DD1") (pin "35") (pinfunction "VCA_35") (pintype "passive"))
      (node (ref "L1") (pin "2") (pinfunction "2_2") (pintype "passive"))
    )
    (net (code "60") (name "VCCA2") (class "Default")
      (node (ref "C7") (pin "2") (pinfunction "2_2") (pintype "passive"))
      (node (ref "DD1") (pin "107") (pinfunction "VCA_107") (pintype "passive"))
      (node (ref "L3") (pin "2") (pinfunction "2_2") (pintype "passive"))
    )
    (net (code "61") (name "VCCIO") (class "Default")
      (node (ref "C17") (pin "2") (pinfunction "2_2") (pintype "passive"))
      (node (ref "C18") (pin "2") (pinfunction "2_2") (pintype "passive"))
      (node (ref "C19") (pin "2") (pinfunction "2_2") (pintype "passive"))
      (node (ref "C20") (pin "2") (pinfunction "2_2") (pintype "passive"))
      (node (ref "C21") (pin "2") (pinfunction "2_2") (pintype "passive"))
      (node (ref "C22") (pin "2") (pinfunction "2_2") (pintype "passive"))
      (node (ref "C23") (pin "2") (pinfunction "2_2") (pintype "passive"))
      (node (ref "C24") (pin "2") (pinfunction "2_2") (pintype "passive"))
      (node (ref "C39") (pin "2") (pinfunction "2_2") (pintype "passive"))
      (node (ref "C4") (pin "2") (pinfunction "2_2") (pintype "passive"))
      (node (ref "C40") (pin "+") (pinfunction "+_+") (pintype "passive"))
      (node (ref "C41") (pin "2") (pinfunction "2_2") (pintype "passive"))
      (node (ref "C42") (pin "2") (pinfunction "2_2") (pintype "passive"))
      (node (ref "C43") (pin "2") (pinfunction "2_2") (pintype "passive"))
      (node (ref "C44") (pin "2") (pinfunction "2_2") (pintype "passive"))
      (node (ref "C5") (pin "2") (pinfunction "2_2") (pintype "passive"))
      (node (ref "DD1") (pin "117") (pinfunction "VCCIO_117") (pintype "passive"))
      (node (ref "DD1") (pin "122") (pinfunction "VCCIO_122") (pintype "passive"))
      (node (ref "DD1") (pin "130") (pinfunction "VCCIO_130") (pintype "passive"))
      (node (ref "DD1") (pin "139") (pinfunction "VCCIO_139") (pintype "passive"))
      (node (ref "DD1") (pin "17") (pinfunction "VCCIO_17") (pintype "passive"))
      (node (ref "DD1") (pin "26") (pinfunction "VCCIO_26") (pintype "passive"))
      (node (ref "DD1") (pin "40") (pinfunction "VCCIO_40") (pintype "passive"))
      (node (ref "DD1") (pin "47") (pinfunction "VCCIO_47") (pintype "passive"))
      (node (ref "DD1") (pin "56") (pinfunction "VCCIO_56") (pintype "passive"))
      (node (ref "DD1") (pin "62") (pinfunction "VCCIO_62") (pintype "passive"))
      (node (ref "DD1") (pin "81") (pinfunction "VCCIO_81") (pintype "passive"))
      (node (ref "DD1") (pin "93") (pinfunction "VCCIO_93") (pintype "passive"))
      (node (ref "DD1") (pin "96") (pinfunction "MSEL1_96") (pintype "passive"))
      (node (ref "DD3") (pin "3") (pinfunction "VCC_3") (pintype "passive"))
      (node (ref "DD3") (pin "7") (pinfunction "VCC_7") (pintype "passive"))
      (node (ref "DD3") (pin "8") (pinfunction "VCC_8") (pintype "passive"))
      (node (ref "L2") (pin "2") (pinfunction "2_2") (pintype "passive"))
      (node (ref "L8") (pin "1") (pinfunction "1_1") (pintype "passive"))
      (node (ref "R3") (pin "2") (pinfunction "2_2") (pintype "passive"))
      (node (ref "R4") (pin "2") (pinfunction "2_2") (pintype "passive"))
      (node (ref "R5") (pin "2") (pinfunction "2_2") (pintype "passive"))
      (node (ref "R6") (pin "2") (pinfunction "2_2") (pintype "passive"))
      (node (ref "R8") (pin "2") (pinfunction "2_2") (pintype "passive"))
      (node (ref "R9") (pin "2") (pinfunction "2_2") (pintype "passive"))
      (node (ref "XP1") (pin "4") (pinfunction "4_4") (pintype "passive"))
    )
    (net (code "62") (name "VCC_PL1") (class "Default")
      (node (ref "C8") (pin "2") (pinfunction "2_2") (pintype "passive"))
      (node (ref "DD1") (pin "37") (pinfunction "VC_PLL_37") (pintype "passive"))
      (node (ref "L4") (pin "2") (pinfunction "2_2") (pintype "passive"))
    )
    (net (code "63") (name "VCC_PL2") (class "Default")
      (node (ref "C9") (pin "2") (pinfunction "2_2") (pintype "passive"))
      (node (ref "DD1") (pin "109") (pinfunction "VC_PLL_109") (pintype "passive"))
      (node (ref "L5") (pin "2") (pinfunction "2_2") (pintype "passive"))
    )
    (net (code "64") (name "VCINT") (class "Default")
      (node (ref "C29") (pin "2") (pinfunction "2_2") (pintype "passive"))
      (node (ref "C30") (pin "+") (pinfunction "+_+") (pintype "passive"))
      (node (ref "C31") (pin "2") (pinfunction "2_2") (pintype "passive"))
      (node (ref "C32") (pin "2") (pinfunction "2_2") (pintype "passive"))
      (node (ref "C33") (pin "2") (pinfunction "2_2") (pintype "passive"))
      (node (ref "C34") (pin "2") (pinfunction "2_2") (pintype "passive"))
      (node (ref "C35") (pin "2") (pinfunction "2_2") (pintype "passive"))
      (node (ref "C36") (pin "2") (pinfunction "2_2") (pintype "passive"))
      (node (ref "C37") (pin "2") (pinfunction "2_2") (pintype "passive"))
      (node (ref "C38") (pin "2") (pinfunction "2_2") (pintype "passive"))
      (node (ref "DD1") (pin "102") (pinfunction "VCINT_102") (pintype "passive"))
      (node (ref "DD1") (pin "116") (pinfunction "VCINT_116") (pintype "passive"))
      (node (ref "DD1") (pin "134") (pinfunction "VCINT_134") (pintype "passive"))
      (node (ref "DD1") (pin "29") (pinfunction "VCINT_29") (pintype "passive"))
      (node (ref "DD1") (pin "45") (pinfunction "VCINT_45") (pintype "passive"))
      (node (ref "DD1") (pin "5") (pinfunction "VCINT_5") (pintype "passive"))
      (node (ref "DD1") (pin "61") (pinfunction "VCINT_61") (pintype "passive"))
      (node (ref "DD1") (pin "78") (pinfunction "VCINT_78") (pintype "passive"))
      (node (ref "L4") (pin "1") (pinfunction "1_1") (pintype "passive"))
      (node (ref "L5") (pin "1") (pinfunction "1_1") (pintype "passive"))
      (node (ref "L7") (pin "2") (pinfunction "2_2") (pintype "passive"))
    )
    (net (code "65") (name "unconnected-(DD1B-I{slash}O-Pad85)") (class "Default")
      (node (ref "DD1") (pin "85") (pinfunction "I/O_85") (pintype "passive"))
    )
    (net (code "66") (name "unconnected-(DD1B-I{slash}O-Pad112)") (class "Default")
      (node (ref "DD1") (pin "112") (pinfunction "I/O_112") (pintype "passive"))
    )
    (net (code "67") (name "unconnected-(DD1C-CLK0-Pad22)") (class "Default")
      (node (ref "DD1") (pin "22") (pinfunction "CLK0_22") (pintype "passive"))
    )
    (net (code "68") (name "unconnected-(DD1C-CLK1-Pad23)") (class "Default")
      (node (ref "DD1") (pin "23") (pinfunction "CLK1_23") (pintype "passive"))
    )
    (net (code "69") (name "unconnected-(DD1C-CLK4-Pad91)") (class "Default")
      (node (ref "DD1") (pin "91") (pinfunction "CLK4_91") (pintype "passive"))
    )
    (net (code "70") (name "unconnected-(DD1C-CLK5-Pad90)") (class "Default")
      (node (ref "DD1") (pin "90") (pinfunction "CLK5_90") (pintype "passive"))
    )
    (net (code "71") (name "unconnected-(DD1C-CLK6-Pad89)") (class "Default")
      (node (ref "DD1") (pin "89") (pinfunction "CLK6_89") (pintype "passive"))
    )
    (net (code "72") (name "unconnected-(DD1C-CLK7-Pad88)") (class "Default")
      (node (ref "DD1") (pin "88") (pinfunction "CLK7_88") (pintype "passive"))
    )
    (net (code "73") (name "unconnected-(DD1C-I{slash}O-Pad1)") (class "Default")
      (node (ref "DD1") (pin "1") (pinfunction "I/O_1") (pintype "passive"))
    )
    (net (code "74") (name "unconnected-(DD1C-I{slash}O-Pad2)") (class "Default")
      (node (ref "DD1") (pin "2") (pinfunction "I/O_2") (pintype "passive"))
    )
    (net (code "75") (name "unconnected-(DD1C-I{slash}O-Pad3)") (class "Default")
      (node (ref "DD1") (pin "3") (pinfunction "I/O_3") (pintype "passive"))
    )
    (net (code "76") (name "unconnected-(DD1C-I{slash}O-Pad4)") (class "Default")
      (node (ref "DD1") (pin "4") (pinfunction "I/O_4") (pintype "passive"))
    )
    (net (code "77") (name "unconnected-(DD1C-I{slash}O-Pad7)") (class "Default")
      (node (ref "DD1") (pin "7") (pinfunction "I/O_7") (pintype "passive"))
    )
    (net (code "78") (name "unconnected-(DD1C-I{slash}O-Pad10)") (class "Default")
      (node (ref "DD1") (pin "10") (pinfunction "I/O_10") (pintype "passive"))
    )
    (net (code "79") (name "unconnected-(DD1C-I{slash}O-Pad11)") (class "Default")
      (node (ref "DD1") (pin "11") (pinfunction "I/O_11") (pintype "passive"))
    )
    (net (code "80") (name "unconnected-(DD1C-I{slash}O-Pad28)") (class "Default")
      (node (ref "DD1") (pin "28") (pinfunction "I/O_28") (pintype "passive"))
    )
    (net (code "81") (name "unconnected-(DD1C-I{slash}O-Pad30)") (class "Default")
      (node (ref "DD1") (pin "30") (pinfunction "I/O_30") (pintype "passive"))
    )
    (net (code "82") (name "unconnected-(DD1C-I{slash}O-Pad33)") (class "Default")
      (node (ref "DD1") (pin "33") (pinfunction "I/O_33") (pintype "passive"))
    )
    (net (code "83") (name "unconnected-(DD1C-I{slash}O-Pad38)") (class "Default")
      (node (ref "DD1") (pin "38") (pinfunction "I/O_38") (pintype "passive"))
    )
    (net (code "84") (name "unconnected-(DD1C-I{slash}O-Pad39)") (class "Default")
      (node (ref "DD1") (pin "39") (pinfunction "I/O_39") (pintype "passive"))
    )
    (net (code "85") (name "unconnected-(DD1C-I{slash}O-Pad42)") (class "Default")
      (node (ref "DD1") (pin "42") (pinfunction "I/O_42") (pintype "passive"))
    )
    (net (code "86") (name "unconnected-(DD1C-I{slash}O-Pad43)") (class "Default")
      (node (ref "DD1") (pin "43") (pinfunction "I/O_43") (pintype "passive"))
    )
    (net (code "87") (name "unconnected-(DD1C-I{slash}O-Pad44)") (class "Default")
      (node (ref "DD1") (pin "44") (pinfunction "I/O_44") (pintype "passive"))
    )
    (net (code "88") (name "unconnected-(DD1C-I{slash}O-Pad46)") (class "Default")
      (node (ref "DD1") (pin "46") (pinfunction "I/O_46") (pintype "passive"))
    )
    (net (code "89") (name "unconnected-(DD1C-I{slash}O-Pad50)") (class "Default")
      (node (ref "DD1") (pin "50") (pinfunction "I/O_50") (pintype "passive"))
    )
    (net (code "90") (name "unconnected-(DD1C-I{slash}O-Pad51)") (class "Default")
      (node (ref "DD1") (pin "51") (pinfunction "I/O_51") (pintype "passive"))
    )
    (net (code "91") (name "unconnected-(DD1C-I{slash}O-Pad52)") (class "Default")
      (node (ref "DD1") (pin "52") (pinfunction "I/O_52") (pintype "passive"))
    )
    (net (code "92") (name "unconnected-(DD1C-I{slash}O-Pad54)") (class "Default")
      (node (ref "DD1") (pin "54") (pinfunction "I/O_54") (pintype "passive"))
    )
    (net (code "93") (name "unconnected-(DD1C-I{slash}O-Pad55)") (class "Default")
      (node (ref "DD1") (pin "55") (pinfunction "I/O_55") (pintype "passive"))
    )
    (net (code "94") (name "unconnected-(DD1C-I{slash}O-Pad64)") (class "Default")
      (node (ref "DD1") (pin "64") (pinfunction "I/O_64") (pintype "passive"))
    )
    (net (code "95") (name "unconnected-(DD1C-I{slash}O-Pad65)") (class "Default")
      (node (ref "DD1") (pin "65") (pinfunction "I/O_65") (pintype "passive"))
    )
    (net (code "96") (name "unconnected-(DD1C-I{slash}O-Pad66)") (class "Default")
      (node (ref "DD1") (pin "66") (pinfunction "I/O_66") (pintype "passive"))
    )
    (net (code "97") (name "unconnected-(DD1C-I{slash}O-Pad67)") (class "Default")
      (node (ref "DD1") (pin "67") (pinfunction "I/O_67") (pintype "passive"))
    )
    (net (code "98") (name "unconnected-(DD1C-I{slash}O-Pad68)") (class "Default")
      (node (ref "DD1") (pin "68") (pinfunction "I/O_68") (pintype "passive"))
    )
    (net (code "99") (name "unconnected-(DD1C-I{slash}O-Pad79)") (class "Default")
      (node (ref "DD1") (pin "79") (pinfunction "I/O_79") (pintype "passive"))
    )
    (net (code "100") (name "unconnected-(DD1C-I{slash}O-Pad86)") (class "Default")
      (node (ref "DD1") (pin "86") (pinfunction "I/O_86") (pintype "passive"))
    )
    (net (code "101") (name "unconnected-(DD1C-I{slash}O-Pad87)") (class "Default")
      (node (ref "DD1") (pin "87") (pinfunction "I/O_87") (pintype "passive"))
    )
    (net (code "102") (name "unconnected-(DD1C-I{slash}O-Pad100)") (class "Default")
      (node (ref "DD1") (pin "100") (pinfunction "I/O_100") (pintype "passive"))
    )
    (net (code "103") (name "unconnected-(DD1C-I{slash}O-Pad101)") (class "Default")
      (node (ref "DD1") (pin "101") (pinfunction "I/O_101") (pintype "passive"))
    )
    (net (code "104") (name "unconnected-(DD1C-I{slash}O-Pad103)") (class "Default")
      (node (ref "DD1") (pin "103") (pinfunction "I/O_103") (pintype "passive"))
    )
    (net (code "105") (name "unconnected-(DD1C-I{slash}O-Pad105)") (class "Default")
      (node (ref "DD1") (pin "105") (pinfunction "I/O_105") (pintype "passive"))
    )
    (net (code "106") (name "unconnected-(DD1C-I{slash}O-Pad106)") (class "Default")
      (node (ref "DD1") (pin "106") (pinfunction "I/O_106") (pintype "passive"))
    )
    (net (code "107") (name "unconnected-(DD1C-I{slash}O-Pad113)") (class "Default")
      (node (ref "DD1") (pin "113") (pinfunction "I/O_113") (pintype "passive"))
    )
    (net (code "108") (name "unconnected-(DD1C-I{slash}O-Pad114)") (class "Default")
      (node (ref "DD1") (pin "114") (pinfunction "I/O_114") (pintype "passive"))
    )
    (net (code "109") (name "unconnected-(DD1C-I{slash}O-Pad128)") (class "Default")
      (node (ref "DD1") (pin "128") (pinfunction "I/O_128") (pintype "passive"))
    )
    (net (code "110") (name "unconnected-(DD1C-I{slash}O-Pad129)") (class "Default")
      (node (ref "DD1") (pin "129") (pinfunction "I/O_129") (pintype "passive"))
    )
    (net (code "111") (name "unconnected-(DD1C-I{slash}O-Pad135)") (class "Default")
      (node (ref "DD1") (pin "135") (pinfunction "I/O_135") (pintype "passive"))
    )
    (net (code "112") (name "unconnected-(DD1C-I{slash}O-Pad141)") (class "Default")
      (node (ref "DD1") (pin "141") (pinfunction "I/O_141") (pintype "passive"))
    )
    (net (code "113") (name "unconnected-(DD1C-I{slash}O-Pad142)") (class "Default")
      (node (ref "DD1") (pin "142") (pinfunction "I/O_142") (pintype "passive"))
    )
    (net (code "114") (name "unconnected-(DD1C-I{slash}O-Pad143)") (class "Default")
      (node (ref "DD1") (pin "143") (pinfunction "I/O_143") (pintype "passive"))
    )
    (net (code "115") (name "unconnected-(DD1C-I{slash}O-Pad144)") (class "Default")
      (node (ref "DD1") (pin "144") (pinfunction "I/O_144") (pintype "passive"))
    )
    (net (code "116") (name "unconnected-(DD2-E{slash}D-Pad1)") (class "Default")
      (node (ref "DD2") (pin "1") (pinfunction "E/D_1") (pintype "passive+no_connect"))
    )
    (net (code "117") (name "unconnected-(XP1-Pad6)") (class "Default")
      (node (ref "XP1") (pin "6") (pinfunction "6_6") (pintype "passive+no_connect"))
    )
    (net (code "118") (name "unconnected-(XP1-Pad7)") (class "Default")
      (node (ref "XP1") (pin "7") (pinfunction "7_7") (pintype "passive+no_connect"))
    )
    (net (code "119") (name "unconnected-(XP1-Pad8)") (class "Default")
      (node (ref "XP1") (pin "8") (pinfunction "8_8") (pintype "passive+no_connect"))
    )
  )
)
